# Schematic_1.net
KiCad netlist of a schematic drawn in Altium Designer
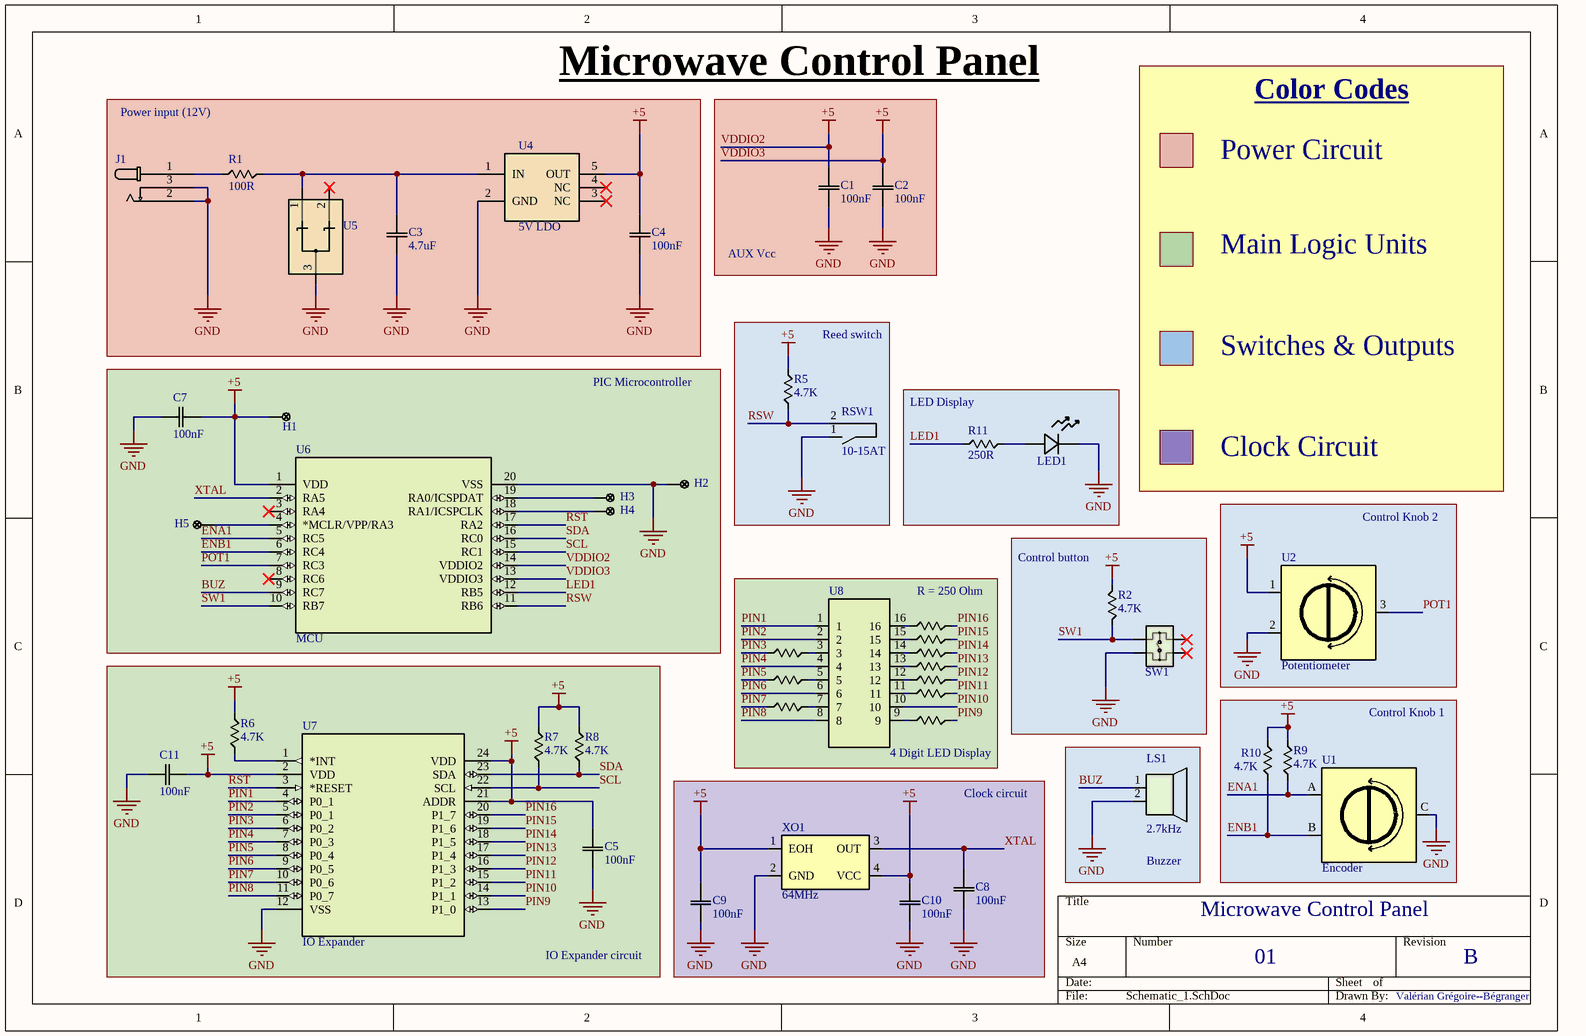
[diagram p0: Schematic_1.SchDoc]

(export (version "E")
  (design (tool "Eeschema 10.0.6"))
  (components
    (comp (ref "C1")
      (value "100nF")
      (footprint "0805_AVX")
      (libsource (lib "Schematic_Library_1") (part "08051C103JAT2A"))
    )
    (comp (ref "C2")
      (value "100nF")
      (footprint "0805_AVX")
      (libsource (lib "Schematic_Library_1") (part "08051C103JAT2A"))
    )
    (comp (ref "C3")
      (value "4.7uF")
      (footprint "CAP_08051A0R8CAT2A_AVX")
      (libsource (lib "Schematic_Library_1") (part "08053C472K4Z2A"))
    )
    (comp (ref "C4")
      (value "100nF")
      (footprint "0805_AVX")
      (libsource (lib "Schematic_Library_1") (part "08051C103JAT2A"))
    )
    (comp (ref "C5")
      (value "100nF")
      (footprint "0805_AVX")
      (libsource (lib "Schematic_Library_1") (part "08051C103JAT2A"))
    )
    (comp (ref "C7")
      (value "100nF")
      (footprint "0805_AVX")
      (libsource (lib "Schematic_Library_1") (part "08051C103JAT2A"))
    )
    (comp (ref "C8")
      (value "100nF")
      (footprint "0805_AVX")
      (libsource (lib "Schematic_Library_1") (part "08051C103JAT2A"))
    )
    (comp (ref "C9")
      (value "100nF")
      (footprint "0805_AVX")
      (libsource (lib "Schematic_Library_1") (part "08051C103JAT2A"))
    )
    (comp (ref "C10")
      (value "100nF")
      (footprint "0805_AVX")
      (libsource (lib "Schematic_Library_1") (part "08051C103JAT2A"))
    )
    (comp (ref "C11")
      (value "100nF")
      (footprint "0805_AVX")
      (libsource (lib "Schematic_Library_1") (part "08051C103JAT2A"))
    )
    (comp (ref "H1")
      (value "Output")
      (footprint "1 pin header")
      (libsource (lib "Schematic_Library_1") (part "1 pin header"))
    )
    (comp (ref "H2")
      (value "Output")
      (footprint "1 pin header")
      (libsource (lib "Schematic_Library_1") (part "1 pin header"))
    )
    (comp (ref "H3")
      (value "Output")
      (footprint "1 pin header")
      (libsource (lib "Schematic_Library_1") (part "1 pin header"))
    )
    (comp (ref "H4")
      (value "Output")
      (footprint "1 pin header")
      (libsource (lib "Schematic_Library_1") (part "1 pin header"))
    )
    (comp (ref "H5")
      (value "Output")
      (footprint "1 pin header")
      (libsource (lib "Schematic_Library_1") (part "1 pin header"))
    )
    (comp (ref "J1")
      (value "PJ-002A")
      (footprint "PJ-002A_CUD")
      (description "DC power plug")
      (libsource (lib "Schematic_Library_1") (part "PJ-002A"))
    )
    (comp (ref "LED1")
      (value "156120VS75300")
      (footprint "LED_VS75300_WRE")
      (description "LED")
      (libsource (lib "Schematic_Library_1") (part "156120VS75300"))
    )
    (comp (ref "LS1")
      (value "2.7kHz")
      (footprint "CMI-9605IC_CUD")
      (description "Buzzer")
      (libsource (lib "Schematic_Library_1") (part "CMI-9605IC-0380T"))
    )
    (comp (ref "R1")
      (value "100R")
      (footprint "0805_VIS")
      (libsource (lib "Schematic_Library_1") (part "RCG080510R0FKEA"))
    )
    (comp (ref "R2")
      (value "4.7K")
      (footprint "RES_1220_SUS")
      (libsource (lib "Schematic_Library_1") (part "RG2012P-472-B-T5"))
    )
    (comp (ref "R3")
      (value "250R")
      (footprint "0805_VIS")
      (libsource (lib "Schematic_Library_1") (part "RNCF0805TKY250R"))
    )
    (comp (ref "R4")
      (value "250R")
      (footprint "0805_VIS")
      (libsource (lib "Schematic_Library_1") (part "RNCF0805TKY250R"))
    )
    (comp (ref "R5")
      (value "4.7K")
      (footprint "RES_1220_SUS")
      (libsource (lib "Schematic_Library_1") (part "RG2012P-472-B-T5"))
    )
    (comp (ref "R6")
      (value "4.7K")
      (footprint "RES_1220_SUS")
      (libsource (lib "Schematic_Library_1") (part "RG2012P-472-B-T5"))
    )
    (comp (ref "R7")
      (value "4.7K")
      (footprint "RES_1220_SUS")
      (libsource (lib "Schematic_Library_1") (part "RG2012P-472-B-T5"))
    )
    (comp (ref "R8")
      (value "4.7K")
      (footprint "RES_1220_SUS")
      (libsource (lib "Schematic_Library_1") (part "RG2012P-472-B-T5"))
    )
    (comp (ref "R9")
      (value "4.7K")
      (footprint "RES_1220_SUS")
      (libsource (lib "Schematic_Library_1") (part "RG2012P-472-B-T5"))
    )
    (comp (ref "R10")
      (value "4.7K")
      (footprint "RES_1220_SUS")
      (libsource (lib "Schematic_Library_1") (part "RG2012P-472-B-T5"))
    )
    (comp (ref "R11")
      (value "250R")
      (footprint "0805_VIS")
      (libsource (lib "Schematic_Library_1") (part "RNCF0805TKY250R"))
    )
    (comp (ref "R12")
      (value "250R")
      (footprint "0805_VIS")
      (libsource (lib "Schematic_Library_1") (part "RNCF0805TKY250R"))
    )
    (comp (ref "R13")
      (value "250R")
      (footprint "0805_VIS")
      (libsource (lib "Schematic_Library_1") (part "RNCF0805TKY250R"))
    )
    (comp (ref "R14")
      (value "250R")
      (footprint "0805_VIS")
      (libsource (lib "Schematic_Library_1") (part "RNCF0805TKY250R"))
    )
    (comp (ref "R15")
      (value "250R")
      (footprint "0805_VIS")
      (libsource (lib "Schematic_Library_1") (part "RNCF0805TKY250R"))
    )
    (comp (ref "R16")
      (value "250R")
      (footprint "0805_VIS")
      (libsource (lib "Schematic_Library_1") (part "RNCF0805TKY250R"))
    )
    (comp (ref "R17")
      (value "250R")
      (footprint "0805_VIS")
      (libsource (lib "Schematic_Library_1") (part "RNCF0805TKY250R"))
    )
    (comp (ref "R18")
      (value "250R")
      (footprint "0805_VIS")
      (libsource (lib "Schematic_Library_1") (part "RNCF0805TKY250R"))
    )
    (comp (ref "R19")
      (value "250R")
      (footprint "0805_VIS")
      (libsource (lib "Schematic_Library_1") (part "RNCF0805TKY250R"))
    )
    (comp (ref "RSW1")
      (value "10-15AT")
      (footprint "GP56010-15")
      (description "Reed switch")
      (libsource (lib "Schematic_Library_1") (part "GP56010-15"))
    )
    (comp (ref "SW1")
      (value "TS02-66-160-BK-100-LCR-D")
      (footprint "TS02-66-160-BK-100-LCR-D")
      (description "Push button")
      (libsource (lib "Schematic_Library_1") (part "TS02-66-160-BK-100-LCR-D"))
    )
    (comp (ref "U1")
      (value "Encoder")
      (footprint "288T232R161A1")
      (description "2b Encoder")
      (libsource (lib "Schematic_Library_1") (part "288T232R161A1"))
    )
    (comp (ref "U2")
      (value "Potentiometer")
      (footprint "2002111655")
      (libsource (lib "Schematic_Library_1") (part "2002111655"))
    )
    (comp (ref "U4")
      (value "5V LDO")
      (footprint "SOT-23-5-DBV_TEX")
      (libsource (lib "Schematic_Library_1") (part "TPS7B92050DBVR"))
    )
    (comp (ref "U5")
      (value "MMBZ16VAT-QR")
      (footprint "SOT_SM712")
      (description "13V TVS")
      (libsource (lib "Schematic_Library_1") (part "MMBZ16VAT-QR"))
    )
    (comp (ref "U6")
      (value "MCU")
      (footprint "SOIC20_SO_MCH")
      (description "PIC MCU")
      (libsource (lib "Schematic_Library_1") (part "PIC18F15Q20T-ISO"))
    )
    (comp (ref "U7")
      (value "IO Expander")
      (footprint "TSSOP24_4P5X7P9_NXP")
      (description "16 I/O expander")
      (libsource (lib "Schematic_Library_1") (part "PCAL6416APW"))
    )
    (comp (ref "U8")
      (value "LED Display")
      (footprint "TDCG1060M_VIS")
      (description "4 digit LED display")
      (libsource (lib "Schematic_Library_1") (part "TDCR1060M"))
    )
    (comp (ref "XO1")
      (value "64MHz")
      (footprint "CB3-3C-64M0000")
      (description "64MHz Clock")
      (libsource (lib "Schematic_Library_1") (part "CB3-3C-64M0000"))
    )
  )
  (nets
    (net (code "1") (name "+5") (class "Default")
      (node (ref "C1") (pin "2") (pinfunction "2_2") (pintype "passive"))
      (node (ref "C10") (pin "2") (pinfunction "2_2") (pintype "passive"))
      (node (ref "C11") (pin "2") (pinfunction "2_2") (pintype "passive"))
      (node (ref "C2") (pin "2") (pinfunction "2_2") (pintype "passive"))
      (node (ref "C4") (pin "2") (pinfunction "2_2") (pintype "passive"))
      (node (ref "C5") (pin "2") (pinfunction "2_2") (pintype "passive"))
      (node (ref "C7") (pin "2") (pinfunction "2_2") (pintype "passive"))
      (node (ref "C9") (pin "2") (pinfunction "2_2") (pintype "passive"))
      (node (ref "H1") (pin "1") (pinfunction "1_1") (pintype "passive"))
      (node (ref "R10") (pin "2") (pinfunction "2_2") (pintype "passive"))
      (node (ref "R2") (pin "2") (pinfunction "2_2") (pintype "passive"))
      (node (ref "R5") (pin "2") (pinfunction "2_2") (pintype "passive"))
      (node (ref "R6") (pin "2") (pinfunction "2_2") (pintype "passive"))
      (node (ref "R7") (pin "2") (pinfunction "2_2") (pintype "passive"))
      (node (ref "R8") (pin "2") (pinfunction "2_2") (pintype "passive"))
      (node (ref "R9") (pin "2") (pinfunction "2_2") (pintype "passive"))
      (node (ref "U2") (pin "1") (pinfunction "1_1") (pintype "passive"))
      (node (ref "U4") (pin "5") (pinfunction "OUT_5") (pintype "passive"))
      (node (ref "U6") (pin "1") (pinfunction "VDD_1") (pintype "passive"))
      (node (ref "U6") (pin "13") (pinfunction "VDDIO3_13") (pintype "bidirectional"))
      (node (ref "U6") (pin "14") (pinfunction "VDDIO2_14") (pintype "bidirectional"))
      (node (ref "U7") (pin "2") (pinfunction "VDD_2") (pintype "passive"))
      (node (ref "U7") (pin "21") (pinfunction "ADDR_21") (pintype "passive"))
      (node (ref "U7") (pin "24") (pinfunction "VDD_24") (pintype "passive"))
      (node (ref "XO1") (pin "1") (pinfunction "EOH_1") (pintype "passive"))
      (node (ref "XO1") (pin "4") (pinfunction "VCC_4") (pintype "passive"))
    )
    (net (code "2") (name "/BUZ") (class "Default")
      (node (ref "LS1") (pin "1") (pinfunction "1_1") (pintype "passive"))
      (node (ref "U6") (pin "9") (pinfunction "RC7_9") (pintype "bidirectional"))
    )
    (net (code "3") (name "/ENA1") (class "Default")
      (node (ref "R9") (pin "1") (pinfunction "1_1") (pintype "passive"))
      (node (ref "U1") (pin "A") (pinfunction "A_A") (pintype "passive"))
      (node (ref "U6") (pin "5") (pinfunction "RC5_5") (pintype "bidirectional"))
    )
    (net (code "4") (name "/ENB1") (class "Default")
      (node (ref "R10") (pin "1") (pinfunction "1_1") (pintype "passive"))
      (node (ref "U1") (pin "B") (pinfunction "B_B") (pintype "passive"))
      (node (ref "U6") (pin "6") (pinfunction "RC4_6") (pintype "bidirectional"))
    )
    (net (code "5") (name "/LED1") (class "Default")
      (node (ref "R11") (pin "1") (pinfunction "1_1") (pintype "passive"))
      (node (ref "U6") (pin "12") (pinfunction "RB5_12") (pintype "bidirectional"))
    )
    (net (code "6") (name "/PIN1") (class "Default")
      (node (ref "U7") (pin "4") (pinfunction "P0_1_4") (pintype "bidirectional"))
      (node (ref "U8") (pin "1") (pinfunction "1_1") (pintype "passive"))
    )
    (net (code "7") (name "/PIN2") (class "Default")
      (node (ref "U7") (pin "5") (pinfunction "P0_1_5") (pintype "bidirectional"))
      (node (ref "U8") (pin "2") (pinfunction "2_2") (pintype "passive"))
    )
    (net (code "8") (name "/PIN3") (class "Default")
      (node (ref "R12") (pin "1") (pinfunction "1_1") (pintype "passive"))
      (node (ref "U7") (pin "6") (pinfunction "P0_2_6") (pintype "bidirectional"))
    )
    (net (code "9") (name "/PIN4") (class "Default")
      (node (ref "U7") (pin "7") (pinfunction "P0_3_7") (pintype "bidirectional"))
      (node (ref "U8") (pin "4") (pinfunction "4_4") (pintype "passive"))
    )
    (net (code "10") (name "/PIN5") (class "Default")
      (node (ref "R15") (pin "1") (pinfunction "1_1") (pintype "passive"))
      (node (ref "U7") (pin "8") (pinfunction "P0_4_8") (pintype "bidirectional"))
    )
    (net (code "11") (name "/PIN6") (class "Default")
      (node (ref "U7") (pin "9") (pinfunction "P0_5_9") (pintype "bidirectional"))
      (node (ref "U8") (pin "6") (pinfunction "6_6") (pintype "passive"))
    )
    (net (code "12") (name "/PIN7") (class "Default")
      (node (ref "R18") (pin "1") (pinfunction "1_1") (pintype "passive"))
      (node (ref "U7") (pin "10") (pinfunction "P0_6_10") (pintype "bidirectional"))
    )
    (net (code "13") (name "/PIN8") (class "Default")
      (node (ref "U7") (pin "11") (pinfunction "P0_7_11") (pintype "bidirectional"))
      (node (ref "U8") (pin "8") (pinfunction "8_8") (pintype "passive"))
    )
    (net (code "14") (name "/PIN9") (class "Default")
      (node (ref "R19") (pin "2") (pinfunction "2_2") (pintype "passive"))
      (node (ref "U7") (pin "13") (pinfunction "P1_0_13") (pintype "bidirectional"))
    )
    (net (code "15") (name "/PIN10") (class "Default")
      (node (ref "U7") (pin "14") (pinfunction "P1_1_14") (pintype "bidirectional"))
      (node (ref "U8") (pin "10") (pinfunction "10_10") (pintype "passive"))
    )
    (net (code "16") (name "/PIN11") (class "Default")
      (node (ref "R17") (pin "2") (pinfunction "2_2") (pintype "passive"))
      (node (ref "U7") (pin "15") (pinfunction "P1_2_15") (pintype "bidirectional"))
    )
    (net (code "17") (name "/PIN12") (class "Default")
      (node (ref "R16") (pin "2") (pinfunction "2_2") (pintype "passive"))
      (node (ref "U7") (pin "16") (pinfunction "P1_3_16") (pintype "bidirectional"))
    )
    (net (code "18") (name "/PIN13") (class "Default")
      (node (ref "R14") (pin "2") (pinfunction "2_2") (pintype "passive"))
      (node (ref "U7") (pin "17") (pinfunction "P1_4_17") (pintype "bidirectional"))
    )
    (net (code "19") (name "/PIN14") (class "Default")
      (node (ref "R13") (pin "2") (pinfunction "2_2") (pintype "passive"))
      (node (ref "U7") (pin "18") (pinfunction "P1_5_18") (pintype "bidirectional"))
    )
    (net (code "20") (name "/PIN15") (class "Default")
      (node (ref "R4") (pin "2") (pinfunction "2_2") (pintype "passive"))
      (node (ref "U7") (pin "19") (pinfunction "P1_6_19") (pintype "bidirectional"))
    )
    (net (code "21") (name "/PIN16") (class "Default")
      (node (ref "R3") (pin "2") (pinfunction "2_2") (pintype "passive"))
      (node (ref "U7") (pin "20") (pinfunction "P1_7_20") (pintype "bidirectional"))
    )
    (net (code "22") (name "/POT1") (class "Default")
      (node (ref "U2") (pin "3") (pinfunction "3_3") (pintype "passive"))
      (node (ref "U6") (pin "7") (pinfunction "RC3_7") (pintype "bidirectional"))
    )
    (net (code "23") (name "/RST") (class "Default")
      (node (ref "U6") (pin "17") (pinfunction "RA2_17") (pintype "bidirectional"))
      (node (ref "U7") (pin "3") (pinfunction "*RESET_3") (pintype "input"))
    )
    (net (code "24") (name "/RSW") (class "Default")
      (node (ref "R5") (pin "1") (pinfunction "1_1") (pintype "passive"))
      (node (ref "RSW1") (pin "2") (pinfunction "2_2") (pintype "passive"))
      (node (ref "U6") (pin "11") (pinfunction "RB6_11") (pintype "bidirectional"))
    )
    (net (code "25") (name "/SCL") (class "Default")
      (node (ref "R7") (pin "1") (pinfunction "1_1") (pintype "passive"))
      (node (ref "U6") (pin "15") (pinfunction "RC1_15") (pintype "bidirectional"))
      (node (ref "U7") (pin "22") (pinfunction "SCL_22") (pintype "input"))
    )
    (net (code "26") (name "/SDA") (class "Default")
      (node (ref "R8") (pin "1") (pinfunction "1_1") (pintype "passive"))
      (node (ref "U6") (pin "16") (pinfunction "RC0_16") (pintype "bidirectional"))
      (node (ref "U7") (pin "23") (pinfunction "SDA_23") (pintype "bidirectional"))
    )
    (net (code "27") (name "/SW1") (class "Default")
      (node (ref "R2") (pin "1") (pinfunction "1_1") (pintype "passive"))
      (node (ref "SW1") (pin "1") (pinfunction "2_1") (pintype "passive"))
      (node (ref "U6") (pin "10") (pinfunction "RB7_10") (pintype "bidirectional"))
    )
    (net (code "28") (name "/XTAL") (class "Default")
      (node (ref "C8") (pin "2") (pinfunction "2_2") (pintype "passive"))
      (node (ref "U6") (pin "2") (pinfunction "RA5_2") (pintype "bidirectional"))
      (node (ref "XO1") (pin "3") (pinfunction "OUT_3") (pintype "passive"))
    )
    (net (code "29") (name "GND") (class "Default")
      (node (ref "C1") (pin "1") (pinfunction "1_1") (pintype "passive"))
      (node (ref "C10") (pin "1") (pinfunction "1_1") (pintype "passive"))
      (node (ref "C11") (pin "1") (pinfunction "1_1") (pintype "passive"))
      (node (ref "C2") (pin "1") (pinfunction "1_1") (pintype "passive"))
      (node (ref "C3") (pin "1") (pinfunction "1_1") (pintype "passive"))
      (node (ref "C4") (pin "1") (pinfunction "1_1") (pintype "passive"))
      (node (ref "C5") (pin "1") (pinfunction "1_1") (pintype "passive"))
      (node (ref "C7") (pin "1") (pinfunction "1_1") (pintype "passive"))
      (node (ref "C8") (pin "1") (pinfunction "1_1") (pintype "passive"))
      (node (ref "C9") (pin "1") (pinfunction "1_1") (pintype "passive"))
      (node (ref "H2") (pin "1") (pinfunction "1_1") (pintype "passive"))
      (node (ref "J1") (pin "2") (pinfunction "2_2") (pintype "passive"))
      (node (ref "J1") (pin "3") (pinfunction "3_3") (pintype "passive"))
      (node (ref "LED1") (pin "1") (pinfunction "1_1") (pintype "passive"))
      (node (ref "LS1") (pin "2") (pinfunction "2_2") (pintype "passive"))
      (node (ref "RSW1") (pin "1") (pinfunction "1_1") (pintype "passive"))
      (node (ref "SW1") (pin "2") (pinfunction "4_2") (pintype "passive"))
      (node (ref "U1") (pin "C") (pinfunction "C_C") (pintype "passive"))
      (node (ref "U2") (pin "2") (pinfunction "2_2") (pintype "passive"))
      (node (ref "U4") (pin "2") (pinfunction "GND_2") (pintype "power_in"))
      (node (ref "U5") (pin "3") (pinfunction "3_3") (pintype "passive"))
      (node (ref "U6") (pin "20") (pinfunction "VSS_20") (pintype "passive"))
      (node (ref "U7") (pin "12") (pinfunction "VSS_12") (pintype "power_in"))
      (node (ref "XO1") (pin "2") (pinfunction "GND_2") (pintype "passive"))
    )
    (net (code "30") (name "Net-(J1-Pad1)") (class "Default")
      (node (ref "J1") (pin "1") (pinfunction "1_1") (pintype "passive"))
      (node (ref "R1") (pin "1") (pinfunction "1_1") (pintype "passive"))
    )
    (net (code "31") (name "Net-(LED1-Pad2)") (class "Default")
      (node (ref "LED1") (pin "2") (pinfunction "2_2") (pintype "passive"))
      (node (ref "R11") (pin "2") (pinfunction "2_2") (pintype "passive"))
    )
    (net (code "32") (name "Net-(R3-Pad1)") (class "Default")
      (node (ref "R3") (pin "1") (pinfunction "1_1") (pintype "passive"))
      (node (ref "U8") (pin "16") (pinfunction "16_16") (pintype "passive"))
    )
    (net (code "33") (name "Net-(R4-Pad1)") (class "Default")
      (node (ref "R4") (pin "1") (pinfunction "1_1") (pintype "passive"))
      (node (ref "U8") (pin "15") (pinfunction "15_15") (pintype "passive"))
    )
    (net (code "34") (name "Net-(R12-Pad2)") (class "Default")
      (node (ref "R12") (pin "2") (pinfunction "2_2") (pintype "passive"))
      (node (ref "U8") (pin "3") (pinfunction "3_3") (pintype "passive"))
    )
    (net (code "35") (name "Net-(R13-Pad1)") (class "Default")
      (node (ref "R13") (pin "1") (pinfunction "1_1") (pintype "passive"))
      (node (ref "U8") (pin "14") (pinfunction "14_14") (pintype "passive"))
    )
    (net (code "36") (name "Net-(R14-Pad1)") (class "Default")
      (node (ref "R14") (pin "1") (pinfunction "1_1") (pintype "passive"))
      (node (ref "U8") (pin "13") (pinfunction "13_13") (pintype "passive"))
    )
    (net (code "37") (name "Net-(R15-Pad2)") (class "Default")
      (node (ref "R15") (pin "2") (pinfunction "2_2") (pintype "passive"))
      (node (ref "U8") (pin "5") (pinfunction "5_5") (pintype "passive"))
    )
    (net (code "38") (name "Net-(R16-Pad1)") (class "Default")
      (node (ref "R16") (pin "1") (pinfunction "1_1") (pintype "passive"))
      (node (ref "U8") (pin "12") (pinfunction "12_12") (pintype "passive"))
    )
    (net (code "39") (name "Net-(R17-Pad1)") (class "Default")
      (node (ref "R17") (pin "1") (pinfunction "1_1") (pintype "passive"))
      (node (ref "U8") (pin "11") (pinfunction "11_11") (pintype "passive"))
    )
    (net (code "40") (name "Net-(R18-Pad2)") (class "Default")
      (node (ref "R18") (pin "2") (pinfunction "2_2") (pintype "passive"))
      (node (ref "U8") (pin "7") (pinfunction "7_7") (pintype "passive"))
    )
    (net (code "41") (name "Net-(R19-Pad1)") (class "Default")
      (node (ref "R19") (pin "1") (pinfunction "1_1") (pintype "passive"))
      (node (ref "U8") (pin "9") (pinfunction "9_9") (pintype "passive"))
    )
    (net (code "42") (name "Net-(U4-IN)") (class "Default")
      (node (ref "C3") (pin "2") (pinfunction "2_2") (pintype "passive"))
      (node (ref "R1") (pin "2") (pinfunction "2_2") (pintype "passive"))
      (node (ref "U4") (pin "1") (pinfunction "IN_1") (pintype "passive"))
      (node (ref "U5") (pin "1") (pinfunction "1_1") (pintype "passive"))
    )
    (net (code "43") (name "Net-(U6-*MCLR{slash}VPP{slash}RA3)") (class "Default")
      (node (ref "H5") (pin "1") (pinfunction "1_1") (pintype "passive"))
      (node (ref "U6") (pin "4") (pinfunction "*MCLR/VPP/RA3_4") (pintype "bidirectional"))
    )
    (net (code "44") (name "Net-(U6-RA0{slash}ICSPDAT)") (class "Default")
      (node (ref "H3") (pin "1") (pinfunction "1_1") (pintype "passive"))
      (node (ref "U6") (pin "19") (pinfunction "RA0/ICSPDAT_19") (pintype "bidirectional"))
    )
    (net (code "45") (name "Net-(U6-RA1{slash}ICSPCLK)") (class "Default")
      (node (ref "H4") (pin "1") (pinfunction "1_1") (pintype "passive"))
      (node (ref "U6") (pin "18") (pinfunction "RA1/ICSPCLK_18") (pintype "bidirectional"))
    )
    (net (code "46") (name "Net-(U7-*INT)") (class "Default")
      (node (ref "R6") (pin "1") (pinfunction "1_1") (pintype "passive"))
      (node (ref "U7") (pin "1") (pinfunction "*INT_1") (pintype "output"))
    )
    (net (code "47") (name "unconnected-(SW1-3-Pad2)") (class "Default")
      (node (ref "SW1") (pin "2") (pinfunction "3_2") (pintype "passive+no_connect"))
    )
    (net (code "48") (name "unconnected-(SW1-Pad1)") (class "Default")
      (node (ref "SW1") (pin "1") (pinfunction "1_1") (pintype "passive+no_connect"))
    )
    (net (code "49") (name "unconnected-(U4-NC-Pad3)") (class "Default")
      (node (ref "U4") (pin "3") (pinfunction "NC_3") (pintype "passive+no_connect"))
    )
    (net (code "50") (name "unconnected-(U4-NC-Pad4)") (class "Default")
      (node (ref "U4") (pin "4") (pinfunction "NC_4") (pintype "passive+no_connect"))
    )
    (net (code "51") (name "unconnected-(U5-Pad2)") (class "Default")
      (node (ref "U5") (pin "2") (pinfunction "2_2") (pintype "passive+no_connect"))
    )
    (net (code "52") (name "unconnected-(U6-RA4-Pad3)") (class "Default")
      (node (ref "U6") (pin "3") (pinfunction "RA4_3") (pintype "bidirectional+no_connect"))
    )
    (net (code "53") (name "unconnected-(U6-RC6-Pad8)") (class "Default")
      (node (ref "U6") (pin "8") (pinfunction "RC6_8") (pintype "bidirectional+no_connect"))
    )
  )
)
